# UKHASnet-avr-sensor.net
KiCad netlist of a schematic drawn in EAGLE
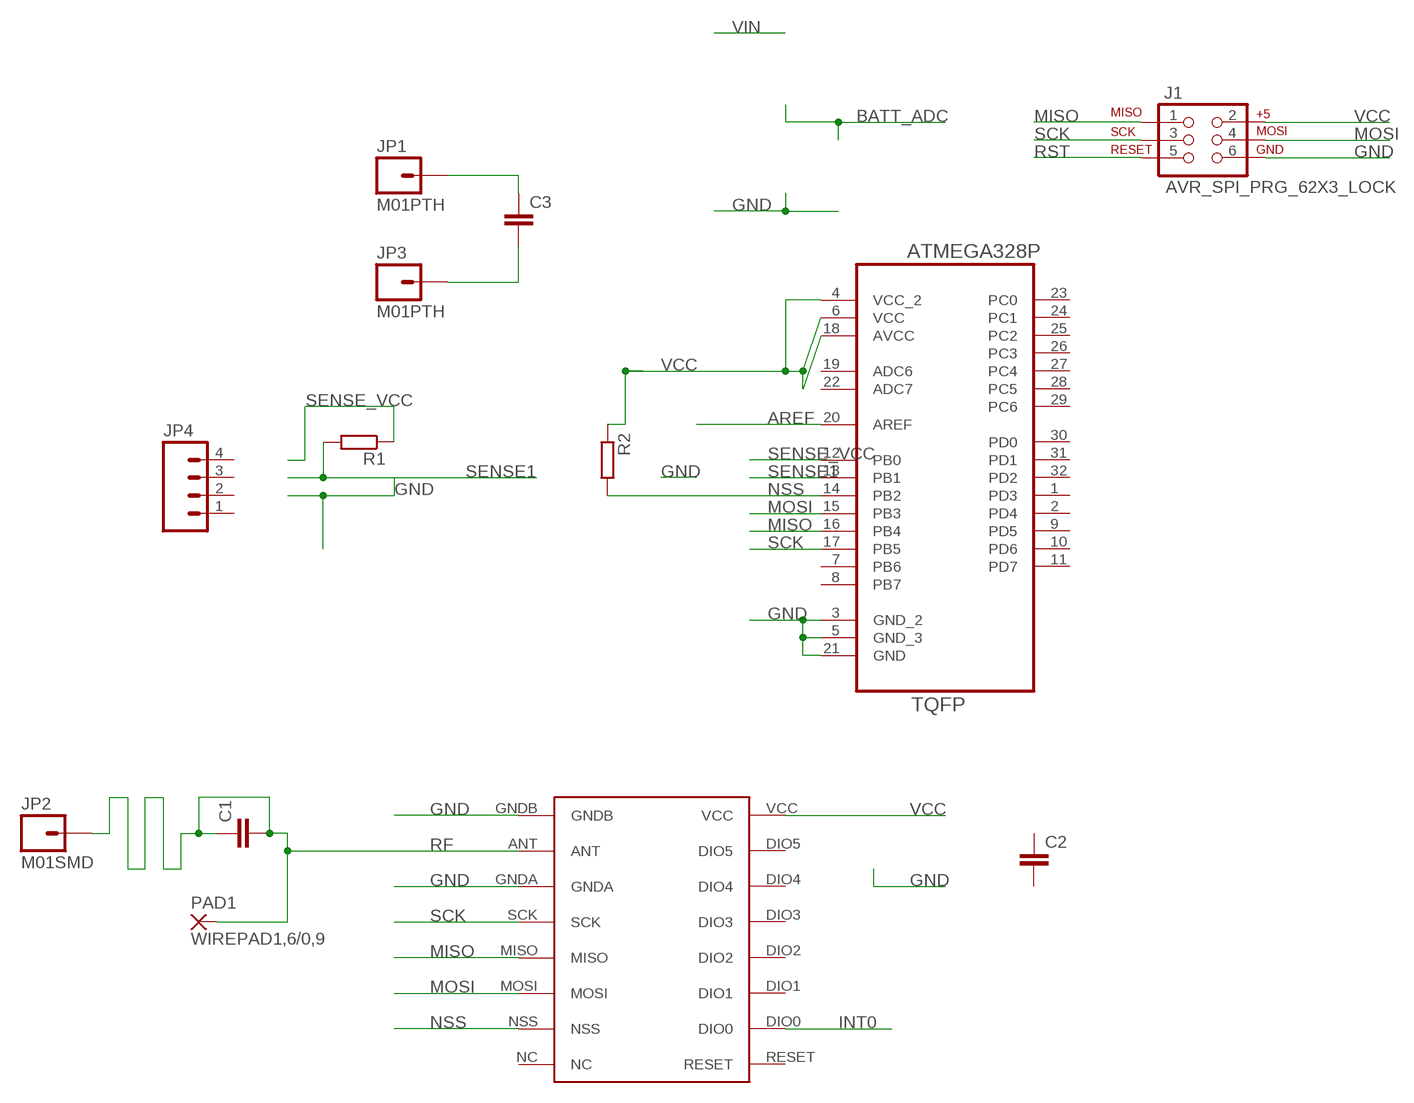
[diagram p0: schematic, sheet 1]

(export (version "E")
  (design (tool "Eeschema 10.0.6"))
  (components
    (comp (ref "C1")
      (value "C-EUC0402")
      (footprint "eagle-import:C0402")
      (libsource (lib "eagle-import") (part "resistor_C-EUC0402"))
    )
    (comp (ref "C2")
      (value "C-EUC0402")
      (footprint "eagle-import:C0402")
      (libsource (lib "eagle-import") (part "resistor_C-EUC0402"))
    )
    (comp (ref "C3")
      (value "C-EUC0402")
      (footprint "eagle-import:C0402")
      (libsource (lib "eagle-import") (part "C-EUC0402"))
    )
    (comp (ref "J1")
      (value "AVR_SPI_PRG_62X3_LOCK")
      (footprint "eagle-import:2X3_LOCK")
      (libsource (lib "eagle-import") (part "AVR_SPI_PRG_62X3_LOCK"))
    )
    (comp (ref "JP1")
      (value "M01PTH")
      (footprint "eagle-import:1X01")
      (libsource (lib "eagle-import") (part "M01PTH"))
    )
    (comp (ref "JP2")
      (value "M01SMD")
      (footprint "eagle-import:LUXEON-PAD")
      (libsource (lib "eagle-import") (part "M01SMD"))
    )
    (comp (ref "JP3")
      (value "M01PTH")
      (footprint "eagle-import:1X01")
      (libsource (lib "eagle-import") (part "M01PTH"))
    )
    (comp (ref "JP4")
      (value "M04PTH")
      (footprint "eagle-import:1X04")
      (libsource (lib "eagle-import") (part "M04PTH"))
    )
    (comp (ref "PAD1")
      (value "WIREPAD1,6/0,9")
      (footprint "eagle-import:1,6_0,9")
      (libsource (lib "eagle-import") (part "WIREPAD1,6/0,9"))
    )
    (comp (ref "R1")
      (value "R-EU_R0402")
      (footprint "eagle-import:R0402")
      (libsource (lib "eagle-import") (part "R-EU_R0402"))
    )
    (comp (ref "R2")
      (value "R-EU_R0402")
      (footprint "eagle-import:R0402")
      (libsource (lib "eagle-import") (part "R-EU_R0402"))
    )
    (comp (ref "U$1")
      (value "RFM69HW")
      (footprint "eagle-import:RFM")
      (libsource (lib "eagle-import") (part "RFM69HW"))
    )
    (comp (ref "U2")
      (value "ATMEGA328P-AU")
      (footprint "eagle-import:QFP80P900X900X120-32N")
      (libsource (lib "eagle-import") (part "ATMEGA328P-AU"))
    )
  )
  (nets
    (net (code "1") (name "/AREF") (class "Default")
      (node (ref "U2") (pin "20") (pinfunction "AREF_20") (pintype "input"))
    )
    (net (code "3") (name "/GND") (class "Default")
      (node (ref "C3") (pin "2") (pinfunction "2_2") (pintype "passive"))
      (node (ref "J1") (pin "6") (pinfunction "6_6") (pintype "passive"))
      (node (ref "JP3") (pin "1") (pinfunction "1_1") (pintype "passive"))
      (node (ref "U$1") (pin "GNDA") (pinfunction "GNDA_GNDA") (pintype "bidirectional"))
      (node (ref "U$1") (pin "GNDB") (pinfunction "GNDB_GNDB") (pintype "bidirectional"))
      (node (ref "U2") (pin "21") (pinfunction "GND_21") (pintype "passive"))
      (node (ref "U2") (pin "3") (pinfunction "GND_2_3") (pintype "passive"))
      (node (ref "U2") (pin "5") (pinfunction "GND_3_5") (pintype "passive"))
    )
    (net (code "4") (name "/INT0") (class "Default")
      (node (ref "U$1") (pin "DIO0") (pinfunction "DIO0_DIO0") (pintype "bidirectional"))
    )
    (net (code "5") (name "/MISO") (class "Default")
      (node (ref "J1") (pin "1") (pinfunction "1_1") (pintype "passive"))
      (node (ref "U$1") (pin "MISO") (pinfunction "MISO_MISO") (pintype "bidirectional"))
      (node (ref "U2") (pin "16") (pinfunction "PB4_16") (pintype "bidirectional"))
    )
    (net (code "6") (name "/MOSI") (class "Default")
      (node (ref "J1") (pin "4") (pinfunction "4_4") (pintype "passive"))
      (node (ref "U$1") (pin "MOSI") (pinfunction "MOSI_MOSI") (pintype "bidirectional"))
      (node (ref "U2") (pin "15") (pinfunction "PB3_15") (pintype "bidirectional"))
    )
    (net (code "7") (name "/NSS") (class "Default")
      (node (ref "R2") (pin "2") (pinfunction "2_2") (pintype "passive"))
      (node (ref "U$1") (pin "NSS") (pinfunction "NSS_NSS") (pintype "bidirectional"))
      (node (ref "U2") (pin "14") (pinfunction "PB2_14") (pintype "bidirectional"))
    )
    (net (code "8") (name "/RF") (class "Default")
      (node (ref "C1") (pin "1") (pinfunction "1_1") (pintype "passive"))
      (node (ref "C1") (pin "2") (pinfunction "2_2") (pintype "passive"))
      (node (ref "JP2") (pin "P$1") (pinfunction "1_P$1") (pintype "passive"))
      (node (ref "PAD1") (pin "1") (pinfunction "P_1") (pintype "passive"))
      (node (ref "U$1") (pin "ANT") (pinfunction "ANT_ANT") (pintype "bidirectional"))
    )
    (net (code "9") (name "/RST") (class "Default")
      (node (ref "J1") (pin "5") (pinfunction "5_5") (pintype "passive"))
    )
    (net (code "10") (name "/SCK") (class "Default")
      (node (ref "J1") (pin "3") (pinfunction "3_3") (pintype "passive"))
      (node (ref "U$1") (pin "SCK") (pinfunction "SCK_SCK") (pintype "bidirectional"))
      (node (ref "U2") (pin "17") (pinfunction "PB5_17") (pintype "bidirectional"))
    )
    (net (code "11") (name "/SENSE1") (class "Default")
      (node (ref "R1") (pin "2") (pinfunction "2_2") (pintype "passive"))
      (node (ref "U2") (pin "13") (pinfunction "PB1_13") (pintype "bidirectional"))
    )
    (net (code "12") (name "/SENSE_VCC") (class "Default")
      (node (ref "R1") (pin "1") (pinfunction "1_1") (pintype "passive"))
      (node (ref "U2") (pin "12") (pinfunction "PB0_12") (pintype "bidirectional"))
    )
    (net (code "13") (name "/VCC") (class "Default")
      (node (ref "C3") (pin "1") (pinfunction "1_1") (pintype "passive"))
      (node (ref "J1") (pin "2") (pinfunction "2_2") (pintype "passive"))
      (node (ref "JP1") (pin "1") (pinfunction "1_1") (pintype "passive"))
      (node (ref "R2") (pin "1") (pinfunction "1_1") (pintype "passive"))
      (node (ref "U$1") (pin "VCC") (pinfunction "VCC_VCC") (pintype "bidirectional"))
      (node (ref "U2") (pin "18") (pinfunction "AVCC_18") (pintype "power_in"))
      (node (ref "U2") (pin "4") (pinfunction "VCC_2_4") (pintype "power_in"))
      (node (ref "U2") (pin "6") (pinfunction "VCC_6") (pintype "power_in"))
    )
    (net (code "15") (name "unconnected-(C2-Pad1)") (class "Default")
      (node (ref "C2") (pin "1") (pinfunction "1_1") (pintype "passive"))
    )
    (net (code "16") (name "unconnected-(C2-Pad2)") (class "Default")
      (node (ref "C2") (pin "2") (pinfunction "2_2") (pintype "passive"))
    )
    (net (code "17") (name "unconnected-(JP4-Pad1)") (class "Default")
      (node (ref "JP4") (pin "1") (pinfunction "1_1") (pintype "passive"))
    )
    (net (code "18") (name "unconnected-(JP4-Pad2)") (class "Default")
      (node (ref "JP4") (pin "2") (pinfunction "2_2") (pintype "passive"))
    )
    (net (code "19") (name "unconnected-(JP4-Pad3)") (class "Default")
      (node (ref "JP4") (pin "3") (pinfunction "3_3") (pintype "passive"))
    )
    (net (code "20") (name "unconnected-(JP4-Pad4)") (class "Default")
      (node (ref "JP4") (pin "4") (pinfunction "4_4") (pintype "passive"))
    )
    (net (code "21") (name "unconnected-(U$1-PadDIO1)") (class "Default")
      (node (ref "U$1") (pin "DIO1") (pinfunction "DIO1_DIO1") (pintype "bidirectional"))
    )
    (net (code "22") (name "unconnected-(U$1-PadDIO2)") (class "Default")
      (node (ref "U$1") (pin "DIO2") (pinfunction "DIO2_DIO2") (pintype "bidirectional"))
    )
    (net (code "23") (name "unconnected-(U$1-PadDIO3)") (class "Default")
      (node (ref "U$1") (pin "DIO3") (pinfunction "DIO3_DIO3") (pintype "bidirectional"))
    )
    (net (code "24") (name "unconnected-(U$1-PadDIO4)") (class "Default")
      (node (ref "U$1") (pin "DIO4") (pinfunction "DIO4_DIO4") (pintype "bidirectional"))
    )
    (net (code "25") (name "unconnected-(U$1-PadDIO5)") (class "Default")
      (node (ref "U$1") (pin "DIO5") (pinfunction "DIO5_DIO5") (pintype "bidirectional"))
    )
    (net (code "26") (name "unconnected-(U$1-PadNC)") (class "Default")
      (node (ref "U$1") (pin "NC") (pinfunction "NC_NC") (pintype "bidirectional"))
    )
    (net (code "27") (name "unconnected-(U$1-PadRESET)") (class "Default")
      (node (ref "U$1") (pin "RESET") (pinfunction "RESET_RESET") (pintype "bidirectional"))
    )
    (net (code "28") (name "unconnected-(U2-ADC6-Pad19)") (class "Default")
      (node (ref "U2") (pin "19") (pinfunction "ADC6_19") (pintype "input"))
    )
    (net (code "29") (name "unconnected-(U2-ADC7-Pad22)") (class "Default")
      (node (ref "U2") (pin "22") (pinfunction "ADC7_22") (pintype "input"))
    )
    (net (code "30") (name "unconnected-(U2-PB6-Pad7)") (class "Default")
      (node (ref "U2") (pin "7") (pinfunction "PB6_7") (pintype "bidirectional"))
    )
    (net (code "31") (name "unconnected-(U2-PB7-Pad8)") (class "Default")
      (node (ref "U2") (pin "8") (pinfunction "PB7_8") (pintype "bidirectional"))
    )
    (net (code "32") (name "unconnected-(U2-PC0-Pad23)") (class "Default")
      (node (ref "U2") (pin "23") (pinfunction "PC0_23") (pintype "bidirectional"))
    )
    (net (code "33") (name "unconnected-(U2-PC1-Pad24)") (class "Default")
      (node (ref "U2") (pin "24") (pinfunction "PC1_24") (pintype "bidirectional"))
    )
    (net (code "34") (name "unconnected-(U2-PC2-Pad25)") (class "Default")
      (node (ref "U2") (pin "25") (pinfunction "PC2_25") (pintype "bidirectional"))
    )
    (net (code "35") (name "unconnected-(U2-PC3-Pad26)") (class "Default")
      (node (ref "U2") (pin "26") (pinfunction "PC3_26") (pintype "bidirectional"))
    )
    (net (code "36") (name "unconnected-(U2-PC4-Pad27)") (class "Default")
      (node (ref "U2") (pin "27") (pinfunction "PC4_27") (pintype "bidirectional"))
    )
    (net (code "37") (name "unconnected-(U2-PC5-Pad28)") (class "Default")
      (node (ref "U2") (pin "28") (pinfunction "PC5_28") (pintype "bidirectional"))
    )
    (net (code "38") (name "unconnected-(U2-PC6-Pad29)") (class "Default")
      (node (ref "U2") (pin "29") (pinfunction "PC6_29") (pintype "bidirectional"))
    )
    (net (code "39") (name "unconnected-(U2-PD0-Pad30)") (class "Default")
      (node (ref "U2") (pin "30") (pinfunction "PD0_30") (pintype "bidirectional"))
    )
    (net (code "40") (name "unconnected-(U2-PD1-Pad31)") (class "Default")
      (node (ref "U2") (pin "31") (pinfunction "PD1_31") (pintype "bidirectional"))
    )
    (net (code "41") (name "unconnected-(U2-PD2-Pad32)") (class "Default")
      (node (ref "U2") (pin "32") (pinfunction "PD2_32") (pintype "bidirectional"))
    )
    (net (code "42") (name "unconnected-(U2-PD3-Pad1)") (class "Default")
      (node (ref "U2") (pin "1") (pinfunction "PD3_1") (pintype "bidirectional"))
    )
    (net (code "43") (name "unconnected-(U2-PD4-Pad2)") (class "Default")
      (node (ref "U2") (pin "2") (pinfunction "PD4_2") (pintype "bidirectional"))
    )
    (net (code "44") (name "unconnected-(U2-PD5-Pad9)") (class "Default")
      (node (ref "U2") (pin "9") (pinfunction "PD5_9") (pintype "bidirectional"))
    )
    (net (code "45") (name "unconnected-(U2-PD6-Pad10)") (class "Default")
      (node (ref "U2") (pin "10") (pinfunction "PD6_10") (pintype "bidirectional"))
    )
    (net (code "46") (name "unconnected-(U2-PD7-Pad11)") (class "Default")
      (node (ref "U2") (pin "11") (pinfunction "PD7_11") (pintype "bidirectional"))
    )
  )
)
